# ws2812-cube-v1_3.net
KiCad netlist of a schematic drawn in EasyEDA
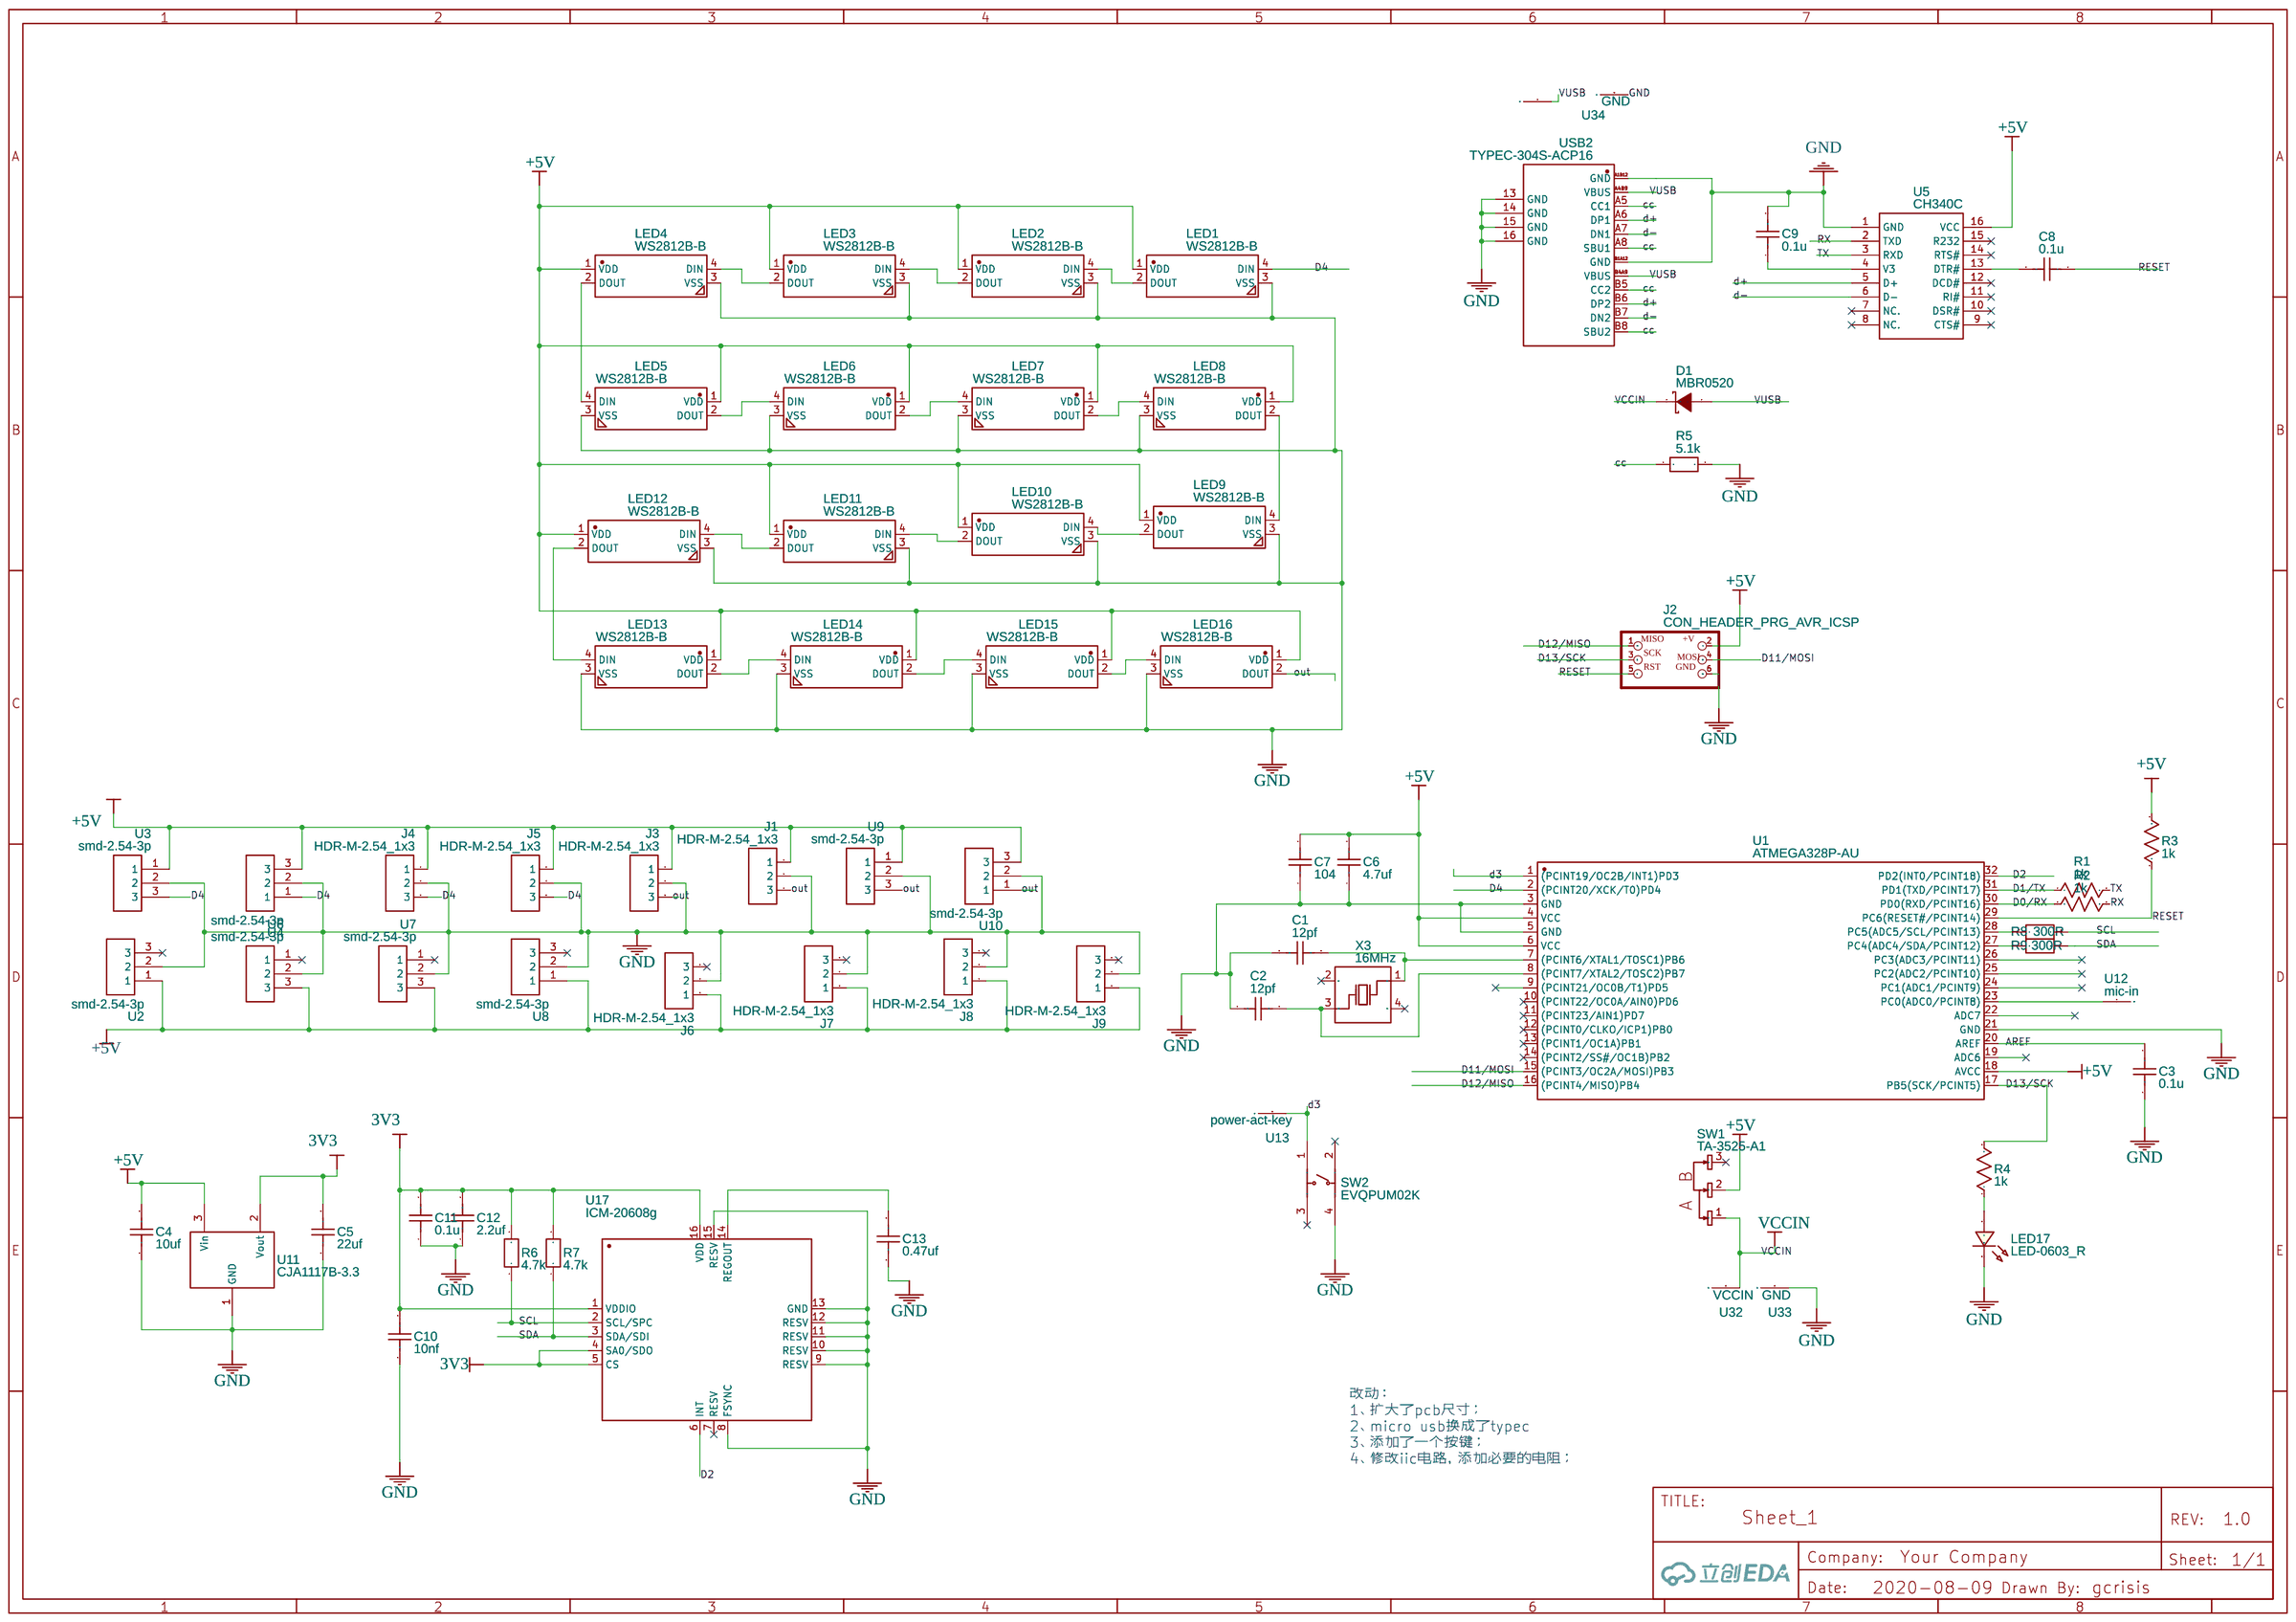
[diagram p0: schematic sheet]

(export (version "E")
  (design (tool "Eeschema 10.0.6"))
  (components
    (comp (ref "C1") (value "12pf") (libsource (lib "") (part "C_0603_US")))
    (comp (ref "C2") (value "12pf") (libsource (lib "") (part "C_0603_US")))
    (comp (ref "C3") (value "0.1u") (libsource (lib "") (part "C_0603_US_1")))
    (comp (ref "C4") (value "10uf") (libsource (lib "") (part "C_0603_US_1")))
    (comp (ref "C5") (value "22uf") (libsource (lib "") (part "C_0603_US_1")))
    (comp (ref "C6") (value "4.7uf") (libsource (lib "") (part "C_0603_US_1")))
    (comp (ref "C7") (value "104") (libsource (lib "") (part "C_0603_US_1")))
    (comp (ref "C8") (value "0.1u") (libsource (lib "") (part "C_0603_US")))
    (comp (ref "C9") (value "0.1u") (libsource (lib "") (part "C_0603_US_1")))
    (comp (ref "C10") (value "10nf") (libsource (lib "") (part "C_0603_US_1")))
    (comp (ref "C11") (value "0.1u") (libsource (lib "") (part "C_0603_US_1")))
    (comp (ref "C12") (value "2.2uf") (libsource (lib "") (part "C_0603_US_1")))
    (comp (ref "C13") (value "0.47uf") (libsource (lib "") (part "C_0603_US_1")))
    (comp (ref "D1")
      (value "MBR0520")
      (fields (field (name "BOM_Supplier Part") "C77335"))
      (libsource (lib "") (part "MBR0520"))
    )
    (comp (ref "J1")
      (value "HDR-M-2.54_1x3")
      (fields (field (name "BOM_Supplier Part") "C180248"))
      (libsource (lib "") (part "HDR-M-2.54_1x3_1"))
    )
    (comp (ref "J2") (value "CON_HEADER_PRG_AVR_ICSP") (libsource (lib "") (part "CON_HEADER_PRG_AVR_ICSP")))
    (comp (ref "J3")
      (value "HDR-M-2.54_1x3")
      (fields (field (name "BOM_Supplier Part") "C180248"))
      (libsource (lib "") (part "HDR-M-2.54_1x3_1"))
    )
    (comp (ref "J4")
      (value "HDR-M-2.54_1x3")
      (fields (field (name "BOM_Supplier Part") "C180248"))
      (libsource (lib "") (part "HDR-M-2.54_1x3_1"))
    )
    (comp (ref "J5")
      (value "HDR-M-2.54_1x3")
      (fields (field (name "BOM_Supplier Part") "C180248"))
      (libsource (lib "") (part "HDR-M-2.54_1x3_1"))
    )
    (comp (ref "J6")
      (value "HDR-M-2.54_1x3")
      (fields (field (name "BOM_Supplier Part") "C180248"))
      (libsource (lib "") (part "HDR-M-2.54_1x3"))
    )
    (comp (ref "J7")
      (value "HDR-M-2.54_1x3")
      (fields (field (name "BOM_Supplier Part") "C180248"))
      (libsource (lib "") (part "HDR-M-2.54_1x3"))
    )
    (comp (ref "J8")
      (value "HDR-M-2.54_1x3")
      (fields (field (name "BOM_Supplier Part") "C180248"))
      (libsource (lib "") (part "HDR-M-2.54_1x3"))
    )
    (comp (ref "J9")
      (value "HDR-M-2.54_1x3")
      (fields (field (name "BOM_Supplier Part") "C180248"))
      (libsource (lib "") (part "HDR-M-2.54_1x3"))
    )
    (comp (ref "LED1")
      (value "WS2812B-B")
      (fields (field (name "BOM_Supplier Part") "C114586"))
      (libsource (lib "") (part "WS2812B-B_1"))
    )
    (comp (ref "LED2")
      (value "WS2812B-B")
      (fields (field (name "BOM_Supplier Part") "C114586"))
      (libsource (lib "") (part "WS2812B-B_1"))
    )
    (comp (ref "LED3")
      (value "WS2812B-B")
      (fields (field (name "BOM_Supplier Part") "C114586"))
      (libsource (lib "") (part "WS2812B-B_1"))
    )
    (comp (ref "LED4")
      (value "WS2812B-B")
      (fields (field (name "BOM_Supplier Part") "C114586"))
      (libsource (lib "") (part "WS2812B-B_1"))
    )
    (comp (ref "LED5")
      (value "WS2812B-B")
      (fields (field (name "BOM_Supplier Part") "C114586"))
      (libsource (lib "") (part "WS2812B-B"))
    )
    (comp (ref "LED6")
      (value "WS2812B-B")
      (fields (field (name "BOM_Supplier Part") "C114586"))
      (libsource (lib "") (part "WS2812B-B"))
    )
    (comp (ref "LED7")
      (value "WS2812B-B")
      (fields (field (name "BOM_Supplier Part") "C114586"))
      (libsource (lib "") (part "WS2812B-B"))
    )
    (comp (ref "LED8")
      (value "WS2812B-B")
      (fields (field (name "BOM_Supplier Part") "C114586"))
      (libsource (lib "") (part "WS2812B-B"))
    )
    (comp (ref "LED9")
      (value "WS2812B-B")
      (fields (field (name "BOM_Supplier Part") "C114586"))
      (libsource (lib "") (part "WS2812B-B_1"))
    )
    (comp (ref "LED10")
      (value "WS2812B-B")
      (fields (field (name "BOM_Supplier Part") "C114586"))
      (libsource (lib "") (part "WS2812B-B_1"))
    )
    (comp (ref "LED11")
      (value "WS2812B-B")
      (fields (field (name "BOM_Supplier Part") "C114586"))
      (libsource (lib "") (part "WS2812B-B_1"))
    )
    (comp (ref "LED12")
      (value "WS2812B-B")
      (fields (field (name "BOM_Supplier Part") "C114586"))
      (libsource (lib "") (part "WS2812B-B_1"))
    )
    (comp (ref "LED13")
      (value "WS2812B-B")
      (fields (field (name "BOM_Supplier Part") "C114586"))
      (libsource (lib "") (part "WS2812B-B"))
    )
    (comp (ref "LED14")
      (value "WS2812B-B")
      (fields (field (name "BOM_Supplier Part") "C114586"))
      (libsource (lib "") (part "WS2812B-B"))
    )
    (comp (ref "LED15")
      (value "WS2812B-B")
      (fields (field (name "BOM_Supplier Part") "C114586"))
      (libsource (lib "") (part "WS2812B-B"))
    )
    (comp (ref "LED16")
      (value "WS2812B-B")
      (fields (field (name "BOM_Supplier Part") "C114586"))
      (libsource (lib "") (part "WS2812B-B"))
    )
    (comp (ref "LED17")
      (value "LED-0603_R")
      (fields
        (field (name "BOM_Manufacturer Part") "19-217/R6C-AL1M2VY/3T")
        (field (name "BOM_Supplier Part") "C72044")
      )
      (libsource (lib "") (part "LED-0603_R"))
    )
    (comp (ref "R1") (value "1k") (libsource (lib "") (part "R_0603_US")))
    (comp (ref "R2") (value "1k") (libsource (lib "") (part "R_0603_US")))
    (comp (ref "R3") (value "1k") (libsource (lib "") (part "R_0603_US_1")))
    (comp (ref "R4") (value "1k") (libsource (lib "") (part "R_0603_US_1")))
    (comp (ref "R5") (value "5.1k") (libsource (lib "") (part "R_0603_EU")))
    (comp (ref "R6") (value "4.7k") (libsource (lib "") (part "R_0603_EU_1")))
    (comp (ref "R7") (value "4.7k") (libsource (lib "") (part "R_0603_EU_1")))
    (comp (ref "R8") (value "300R") (libsource (lib "") (part "R_0603_EU")))
    (comp (ref "R9") (value "300R") (libsource (lib "") (part "R_0603_EU")))
    (comp (ref "SW1")
      (value "TA-3525-A1")
      (fields (field (name "BOM_Supplier Part") "C514018"))
      (libsource (lib "") (part "TA-3525-A1"))
    )
    (comp (ref "SW2")
      (value "EVQPUM02K")
      (fields (field (name "BOM_Supplier Part") "C388886"))
      (libsource (lib "") (part "EVQPUM02K"))
    )
    (comp (ref "U1")
      (value "ATMEGA328P-AU")
      (fields (field (name "BOM_Supplier Part") "C14877"))
      (libsource (lib "") (part "ATMEGA328P-AU"))
    )
    (comp (ref "U2") (value "smd-2.54-3p") (libsource (lib "") (part "smd-2.54-3p")))
    (comp (ref "U3") (value "smd-2.54-3p") (libsource (lib "") (part "smd-2.54-3p_1")))
    (comp (ref "U4") (value "smd-2.54-3p") (libsource (lib "") (part "smd-2.54-3p")))
    (comp (ref "U5")
      (value "CH340C")
      (fields (field (name "BOM_Supplier Part") "C84681"))
      (libsource (lib "") (part "CH340C"))
    )
    (comp (ref "U6") (value "smd-2.54-3p") (libsource (lib "") (part "smd-2.54-3p_1")))
    (comp (ref "U7") (value "smd-2.54-3p") (libsource (lib "") (part "smd-2.54-3p_1")))
    (comp (ref "U8") (value "smd-2.54-3p") (libsource (lib "") (part "smd-2.54-3p")))
    (comp (ref "U9") (value "smd-2.54-3p") (libsource (lib "") (part "smd-2.54-3p_1")))
    (comp (ref "U10") (value "smd-2.54-3p") (libsource (lib "") (part "smd-2.54-3p")))
    (comp (ref "U11")
      (value "CJA1117B-3.3")
      (fields (field (name "BOM_Supplier Part") "C24253"))
      (libsource (lib "") (part "CJA1117B-3.3"))
    )
    (comp (ref "U12") (value "mic-in") (libsource (lib "") (part "PAD_1")))
    (comp (ref "U13") (value "power-act-key") (libsource (lib "") (part "PAD")))
    (comp (ref "U17")
      (value "ICM-20608g")
      (fields (field (name "BOM_Manufacturer Part") "ICM-20602") (field (name "BOM_Supplier Part") "C97633"))
      (libsource (lib "") (part "ICM-20602"))
    )
    (comp (ref "U32") (value "VCCIN") (libsource (lib "") (part "PAD")))
    (comp (ref "U33") (value "GND") (libsource (lib "") (part "PAD")))
    (comp (ref "U34") (value "GND") (libsource (lib "") (part "PAD")))
    (comp (ref "U35") (value "VUSB") (libsource (lib "") (part "PAD")))
    (comp (ref "USB2")
      (value "TYPEC-304S-ACP16")
      (fields (field (name "BOM_Supplier Part") "C720630"))
      (libsource (lib "") (part "TYPEC-304S-ACP16"))
    )
    (comp (ref "X3")
      (value "16MHz")
      (fields
        (field (name "BOM_Manufacturer Part") "X1E0000210375000G")
        (field (name "BOM_Supplier Part") "C89379")
      )
      (libsource (lib "") (part "X1E0000210375000G"))
    )
  )
  (nets
    (net (code "1") (name "+5V") (class "Default")
      (node (ref "C4") (pin "2") (pinfunction "2_2") (pintype "unspecified"))
      (node (ref "C6") (pin "2") (pinfunction "2_2") (pintype "unspecified"))
      (node (ref "C7") (pin "2") (pinfunction "2_2") (pintype "unspecified"))
      (node (ref "J1") (pin "1") (pinfunction "1_1") (pintype "input"))
      (node (ref "J2") (pin "2") (pinfunction "+V_2") (pintype "unspecified"))
      (node (ref "J3") (pin "1") (pinfunction "1_1") (pintype "input"))
      (node (ref "J4") (pin "1") (pinfunction "1_1") (pintype "input"))
      (node (ref "J5") (pin "1") (pinfunction "1_1") (pintype "input"))
      (node (ref "J6") (pin "1") (pinfunction "1_1") (pintype "input"))
      (node (ref "J7") (pin "1") (pinfunction "1_1") (pintype "input"))
      (node (ref "J8") (pin "1") (pinfunction "1_1") (pintype "input"))
      (node (ref "J9") (pin "1") (pinfunction "1_1") (pintype "input"))
      (node (ref "LED1") (pin "1") (pinfunction "VDD_1") (pintype "unspecified"))
      (node (ref "LED10") (pin "1") (pinfunction "VDD_1") (pintype "unspecified"))
      (node (ref "LED11") (pin "1") (pinfunction "VDD_1") (pintype "unspecified"))
      (node (ref "LED12") (pin "1") (pinfunction "VDD_1") (pintype "unspecified"))
      (node (ref "LED13") (pin "1") (pinfunction "VDD_1") (pintype "unspecified"))
      (node (ref "LED14") (pin "1") (pinfunction "VDD_1") (pintype "unspecified"))
      (node (ref "LED15") (pin "1") (pinfunction "VDD_1") (pintype "unspecified"))
      (node (ref "LED16") (pin "1") (pinfunction "VDD_1") (pintype "unspecified"))
      (node (ref "LED2") (pin "1") (pinfunction "VDD_1") (pintype "unspecified"))
      (node (ref "LED3") (pin "1") (pinfunction "VDD_1") (pintype "unspecified"))
      (node (ref "LED4") (pin "1") (pinfunction "VDD_1") (pintype "unspecified"))
      (node (ref "LED5") (pin "1") (pinfunction "VDD_1") (pintype "unspecified"))
      (node (ref "LED6") (pin "1") (pinfunction "VDD_1") (pintype "unspecified"))
      (node (ref "LED7") (pin "1") (pinfunction "VDD_1") (pintype "unspecified"))
      (node (ref "LED8") (pin "1") (pinfunction "VDD_1") (pintype "unspecified"))
      (node (ref "LED9") (pin "1") (pinfunction "VDD_1") (pintype "unspecified"))
      (node (ref "R3") (pin "2") (pinfunction "2_2") (pintype "unspecified"))
      (node (ref "SW1") (pin "2") (pinfunction "2_2") (pintype "unspecified"))
      (node (ref "U1") (pin "18") (pinfunction "AVCC_18") (pintype "unspecified"))
      (node (ref "U1") (pin "4") (pinfunction "VCC_4") (pintype "unspecified"))
      (node (ref "U1") (pin "6") (pinfunction "VCC_6") (pintype "unspecified"))
      (node (ref "U10") (pin "3") (pinfunction "3_3") (pintype "unspecified"))
      (node (ref "U11") (pin "3") (pinfunction "Vin_3") (pintype "unspecified"))
      (node (ref "U2") (pin "1") (pinfunction "1_1") (pintype "unspecified"))
      (node (ref "U3") (pin "1") (pinfunction "1_1") (pintype "unspecified"))
      (node (ref "U4") (pin "3") (pinfunction "3_3") (pintype "unspecified"))
      (node (ref "U5") (pin "16") (pinfunction "VCC_16") (pintype "unspecified"))
      (node (ref "U6") (pin "3") (pinfunction "3_3") (pintype "unspecified"))
      (node (ref "U7") (pin "3") (pinfunction "3_3") (pintype "unspecified"))
      (node (ref "U8") (pin "1") (pinfunction "1_1") (pintype "unspecified"))
      (node (ref "U9") (pin "1") (pinfunction "1_1") (pintype "unspecified"))
    )
    (net (code "2") (name "/AREF") (class "Default")
      (node (ref "C3") (pin "2") (pinfunction "2_2") (pintype "unspecified"))
      (node (ref "U1") (pin "20") (pinfunction "AREF_20") (pintype "unspecified"))
    )
    (net (code "3") (name "/D0{slash}RX") (class "Default")
      (node (ref "R2") (pin "1") (pinfunction "1_1") (pintype "unspecified"))
      (node (ref "U1") (pin "30") (pinfunction "PD0(RXD/PCINT16)_30") (pintype "unspecified"))
    )
    (net (code "4") (name "/D1{slash}TX") (class "Default")
      (node (ref "R1") (pin "1") (pinfunction "1_1") (pintype "unspecified"))
      (node (ref "U1") (pin "31") (pinfunction "PD1(TXD/PCINT17)_31") (pintype "unspecified"))
    )
    (net (code "5") (name "/D2") (class "Default")
      (node (ref "U1") (pin "32") (pinfunction "PD2(INT0/PCINT18)_32") (pintype "unspecified"))
      (node (ref "U17") (pin "6") (pinfunction "INT_6") (pintype "unspecified"))
    )
    (net (code "6") (name "/D4") (class "Default")
      (node (ref "J4") (pin "3") (pinfunction "3_3") (pintype "input"))
      (node (ref "J5") (pin "3") (pinfunction "3_3") (pintype "input"))
      (node (ref "LED1") (pin "4") (pinfunction "DIN_4") (pintype "unspecified"))
      (node (ref "U1") (pin "2") (pinfunction "(PCINT20/XCK/T0)PD4_2") (pintype "unspecified"))
      (node (ref "U3") (pin "3") (pinfunction "3_3") (pintype "unspecified"))
      (node (ref "U4") (pin "1") (pinfunction "1_1") (pintype "unspecified"))
    )
    (net (code "7") (name "/D11{slash}MOSI") (class "Default")
      (node (ref "J2") (pin "4") (pinfunction "MOSI_4") (pintype "unspecified"))
      (node (ref "U1") (pin "15") (pinfunction "(PCINT3/OC2A/MOSI)PB3_15") (pintype "unspecified"))
    )
    (net (code "8") (name "/D12{slash}MISO") (class "Default")
      (node (ref "J2") (pin "1") (pinfunction "MISO_1") (pintype "unspecified"))
      (node (ref "U1") (pin "16") (pinfunction "(PCINT4/MISO)PB4_16") (pintype "unspecified"))
    )
    (net (code "9") (name "/D13{slash}SCK") (class "Default")
      (node (ref "J2") (pin "3") (pinfunction "SCK_3") (pintype "unspecified"))
      (node (ref "R4") (pin "2") (pinfunction "2_2") (pintype "unspecified"))
      (node (ref "U1") (pin "17") (pinfunction "PB5(SCK/PCINT5)_17") (pintype "unspecified"))
    )
    (net (code "10") (name "/RESET") (class "Default")
      (node (ref "C8") (pin "2") (pinfunction "2_2") (pintype "unspecified"))
      (node (ref "J2") (pin "5") (pinfunction "RST_5") (pintype "unspecified"))
      (node (ref "R3") (pin "1") (pinfunction "1_1") (pintype "unspecified"))
      (node (ref "U1") (pin "29") (pinfunction "PC6(RESET#/PCINT14)_29") (pintype "unspecified"))
    )
    (net (code "11") (name "/RX") (class "Default")
      (node (ref "R2") (pin "2") (pinfunction "2_2") (pintype "unspecified"))
      (node (ref "U5") (pin "2") (pinfunction "TXD_2") (pintype "unspecified"))
    )
    (net (code "12") (name "/SCL") (class "Default")
      (node (ref "R6") (pin "1") (pinfunction "1_1") (pintype "unspecified"))
      (node (ref "R8") (pin "2") (pinfunction "2_2") (pintype "unspecified"))
      (node (ref "U17") (pin "2") (pinfunction "SCL/SPC_2") (pintype "unspecified"))
    )
    (net (code "13") (name "/SDA") (class "Default")
      (node (ref "R7") (pin "1") (pinfunction "1_1") (pintype "unspecified"))
      (node (ref "R9") (pin "2") (pinfunction "2_2") (pintype "unspecified"))
      (node (ref "U17") (pin "3") (pinfunction "SDA/SDI_3") (pintype "unspecified"))
    )
    (net (code "14") (name "/TX") (class "Default")
      (node (ref "R1") (pin "2") (pinfunction "2_2") (pintype "unspecified"))
      (node (ref "U5") (pin "3") (pinfunction "RXD_3") (pintype "unspecified"))
    )
    (net (code "15") (name "/VUSB") (class "Default")
      (node (ref "D1") (pin "2") (pinfunction "A_2") (pintype "unspecified"))
      (node (ref "U35") (pin "P$1") (pinfunction "P$1_P$1") (pintype "unspecified"))
      (node (ref "USB2") (pin "A4B9") (pinfunction "VBUS_A4B9") (pintype "unspecified"))
      (node (ref "USB2") (pin "B4A9") (pinfunction "VBUS_B4A9") (pintype "unspecified"))
    )
    (net (code "16") (name "/cc") (class "Default")
      (node (ref "R5") (pin "1") (pinfunction "1_1") (pintype "unspecified"))
      (node (ref "USB2") (pin "A5") (pinfunction "CC1_A5") (pintype "unspecified"))
      (node (ref "USB2") (pin "A8") (pinfunction "SBU1_A8") (pintype "unspecified"))
      (node (ref "USB2") (pin "B5") (pinfunction "CC2_B5") (pintype "unspecified"))
      (node (ref "USB2") (pin "B8") (pinfunction "SBU2_B8") (pintype "unspecified"))
    )
    (net (code "17") (name "/d+") (class "Default")
      (node (ref "U5") (pin "5") (pinfunction "D+_5") (pintype "unspecified"))
      (node (ref "USB2") (pin "A6") (pinfunction "DP1_A6") (pintype "unspecified"))
      (node (ref "USB2") (pin "B6") (pinfunction "DP2_B6") (pintype "unspecified"))
    )
    (net (code "18") (name "/d-") (class "Default")
      (node (ref "U5") (pin "6") (pinfunction "D-_6") (pintype "unspecified"))
      (node (ref "USB2") (pin "A7") (pinfunction "DN1_A7") (pintype "unspecified"))
      (node (ref "USB2") (pin "B7") (pinfunction "DN2_B7") (pintype "unspecified"))
    )
    (net (code "19") (name "/d3") (class "Default")
      (node (ref "SW2") (pin "1") (pinfunction "1_1") (pintype "unspecified"))
      (node (ref "U1") (pin "1") (pinfunction "(PCINT19/OC2B/INT1)PD3_1") (pintype "unspecified"))
      (node (ref "U13") (pin "P$1") (pinfunction "P$1_P$1") (pintype "unspecified"))
    )
    (net (code "20") (name "/out") (class "Default")
      (node (ref "J1") (pin "3") (pinfunction "3_3") (pintype "input"))
      (node (ref "J3") (pin "3") (pinfunction "3_3") (pintype "input"))
      (node (ref "LED16") (pin "2") (pinfunction "DOUT_2") (pintype "unspecified"))
      (node (ref "U10") (pin "1") (pinfunction "1_1") (pintype "unspecified"))
      (node (ref "U9") (pin "3") (pinfunction "3_3") (pintype "unspecified"))
    )
    (net (code "21") (name "3V3") (class "Default")
      (node (ref "C10") (pin "2") (pinfunction "2_2") (pintype "unspecified"))
      (node (ref "C11") (pin "2") (pinfunction "2_2") (pintype "unspecified"))
      (node (ref "C12") (pin "2") (pinfunction "2_2") (pintype "unspecified"))
      (node (ref "C5") (pin "2") (pinfunction "2_2") (pintype "unspecified"))
      (node (ref "R6") (pin "2") (pinfunction "2_2") (pintype "unspecified"))
      (node (ref "R7") (pin "2") (pinfunction "2_2") (pintype "unspecified"))
      (node (ref "U11") (pin "2") (pinfunction "Vout_2") (pintype "unspecified"))
      (node (ref "U17") (pin "1") (pinfunction "VDDIO_1") (pintype "unspecified"))
      (node (ref "U17") (pin "16") (pinfunction "VDD_16") (pintype "unspecified"))
      (node (ref "U17") (pin "4") (pinfunction "SA0/SDO_4") (pintype "unspecified"))
      (node (ref "U17") (pin "5") (pinfunction "CS_5") (pintype "unspecified"))
    )
    (net (code "22") (name "GND") (class "Default")
      (node (ref "C1") (pin "1") (pinfunction "1_1") (pintype "unspecified"))
      (node (ref "C10") (pin "1") (pinfunction "1_1") (pintype "unspecified"))
      (node (ref "C11") (pin "1") (pinfunction "1_1") (pintype "unspecified"))
      (node (ref "C12") (pin "1") (pinfunction "1_1") (pintype "unspecified"))
      (node (ref "C13") (pin "1") (pinfunction "1_1") (pintype "unspecified"))
      (node (ref "C2") (pin "1") (pinfunction "1_1") (pintype "unspecified"))
      (node (ref "C3") (pin "1") (pinfunction "1_1") (pintype "unspecified"))
      (node (ref "C4") (pin "1") (pinfunction "1_1") (pintype "unspecified"))
      (node (ref "C5") (pin "1") (pinfunction "1_1") (pintype "unspecified"))
      (node (ref "C6") (pin "1") (pinfunction "1_1") (pintype "unspecified"))
      (node (ref "C7") (pin "1") (pinfunction "1_1") (pintype "unspecified"))
      (node (ref "C9") (pin "2") (pinfunction "2_2") (pintype "unspecified"))
      (node (ref "J1") (pin "2") (pinfunction "2_2") (pintype "input"))
      (node (ref "J2") (pin "6") (pinfunction "GND_6") (pintype "unspecified"))
      (node (ref "J3") (pin "2") (pinfunction "2_2") (pintype "input"))
      (node (ref "J4") (pin "2") (pinfunction "2_2") (pintype "input"))
      (node (ref "J5") (pin "2") (pinfunction "2_2") (pintype "input"))
      (node (ref "J6") (pin "2") (pinfunction "2_2") (pintype "input"))
      (node (ref "J7") (pin "2") (pinfunction "2_2") (pintype "input"))
      (node (ref "J8") (pin "2") (pinfunction "2_2") (pintype "input"))
      (node (ref "J9") (pin "2") (pinfunction "2_2") (pintype "input"))
      (node (ref "LED1") (pin "3") (pinfunction "VSS_3") (pintype "unspecified"))
      (node (ref "LED10") (pin "3") (pinfunction "VSS_3") (pintype "unspecified"))
      (node (ref "LED11") (pin "3") (pinfunction "VSS_3") (pintype "unspecified"))
      (node (ref "LED12") (pin "3") (pinfunction "VSS_3") (pintype "unspecified"))
      (node (ref "LED13") (pin "3") (pinfunction "VSS_3") (pintype "unspecified"))
      (node (ref "LED14") (pin "3") (pinfunction "VSS_3") (pintype "unspecified"))
      (node (ref "LED15") (pin "3") (pinfunction "VSS_3") (pintype "unspecified"))
      (node (ref "LED16") (pin "3") (pinfunction "VSS_3") (pintype "unspecified"))
      (node (ref "LED17") (pin "2") (pinfunction "2_2") (pintype "unspecified"))
      (node (ref "LED2") (pin "3") (pinfunction "VSS_3") (pintype "unspecified"))
      (node (ref "LED3") (pin "3") (pinfunction "VSS_3") (pintype "unspecified"))
      (node (ref "LED4") (pin "3") (pinfunction "VSS_3") (pintype "unspecified"))
      (node (ref "LED5") (pin "3") (pinfunction "VSS_3") (pintype "unspecified"))
      (node (ref "LED6") (pin "3") (pinfunction "VSS_3") (pintype "unspecified"))
      (node (ref "LED7") (pin "3") (pinfunction "VSS_3") (pintype "unspecified"))
      (node (ref "LED8") (pin "3") (pinfunction "VSS_3") (pintype "unspecified"))
      (node (ref "LED9") (pin "3") (pinfunction "VSS_3") (pintype "unspecified"))
      (node (ref "R5") (pin "2") (pinfunction "2_2") (pintype "unspecified"))
      (node (ref "SW2") (pin "4") (pinfunction "4_4") (pintype "unspecified"))
      (node (ref "U1") (pin "21") (pinfunction "GND_21") (pintype "unspecified"))
      (node (ref "U1") (pin "3") (pinfunction "GND_3") (pintype "unspecified"))
      (node (ref "U1") (pin "5") (pinfunction "GND_5") (pintype "unspecified"))
      (node (ref "U10") (pin "2") (pinfunction "2_2") (pintype "unspecified"))
      (node (ref "U11") (pin "1") (pinfunction "GND_1") (pintype "unspecified"))
      (node (ref "U17") (pin "10") (pinfunction "RESV_10") (pintype "unspecified"))
      (node (ref "U17") (pin "11") (pinfunction "RESV_11") (pintype "unspecified"))
      (node (ref "U17") (pin "12") (pinfunction "RESV_12") (pintype "unspecified"))
      (node (ref "U17") (pin "13") (pinfunction "GND_13") (pintype "unspecified"))
      (node (ref "U17") (pin "15") (pinfunction "RESV_15") (pintype "unspecified"))
      (node (ref "U17") (pin "8") (pinfunction "FSYNC_8") (pintype "unspecified"))
      (node (ref "U17") (pin "9") (pinfunction "RESV_9") (pintype "unspecified"))
      (node (ref "U2") (pin "2") (pinfunction "2_2") (pintype "unspecified"))
      (node (ref "U3") (pin "2") (pinfunction "2_2") (pintype "unspecified"))
      (node (ref "U33") (pin "P$1") (pinfunction "P$1_P$1") (pintype "unspecified"))
      (node (ref "U34") (pin "P$1") (pinfunction "P$1_P$1") (pintype "unspecified"))
      (node (ref "U4") (pin "2") (pinfunction "2_2") (pintype "unspecified"))
      (node (ref "U5") (pin "1") (pinfunction "GND_1") (pintype "unspecified"))
      (node (ref "U6") (pin "2") (pinfunction "2_2") (pintype "unspecified"))
      (node (ref "U7") (pin "2") (pinfunction "2_2") (pintype "unspecified"))
      (node (ref "U8") (pin "2") (pinfunction "2_2") (pintype "unspecified"))
      (node (ref "U9") (pin "2") (pinfunction "2_2") (pintype "unspecified"))
      (node (ref "USB2") (pin "13") (pinfunction "GND_13") (pintype "unspecified"))
      (node (ref "USB2") (pin "14") (pinfunction "GND_14") (pintype "unspecified"))
      (node (ref "USB2") (pin "15") (pinfunction "GND_15") (pintype "unspecified"))
      (node (ref "USB2") (pin "16") (pinfunction "GND_16") (pintype "unspecified"))
      (node (ref "USB2") (pin "A1B12") (pinfunction "GND_A1B12") (pintype "unspecified"))
      (node (ref "USB2") (pin "B1A12") (pinfunction "GND_B1A12") (pintype "unspecified"))
    )
    (net (code "23") (name "Net-(LED1-DOUT)") (class "Default")
      (node (ref "LED1") (pin "2") (pinfunction "DOUT_2") (pintype "unspecified"))
      (node (ref "LED2") (pin "4") (pinfunction "DIN_4") (pintype "unspecified"))
    )
    (net (code "24") (name "Net-(LED2-DOUT)") (class "Default")
      (node (ref "LED2") (pin "2") (pinfunction "DOUT_2") (pintype "unspecified"))
      (node (ref "LED3") (pin "4") (pinfunction "DIN_4") (pintype "unspecified"))
    )
    (net (code "25") (name "Net-(LED3-DOUT)") (class "Default")
      (node (ref "LED3") (pin "2") (pinfunction "DOUT_2") (pintype "unspecified"))
      (node (ref "LED4") (pin "4") (pinfunction "DIN_4") (pintype "unspecified"))
    )
    (net (code "26") (name "Net-(LED4-DOUT)") (class "Default")
      (node (ref "LED4") (pin "2") (pinfunction "DOUT_2") (pintype "unspecified"))
      (node (ref "LED5") (pin "4") (pinfunction "DIN_4") (pintype "unspecified"))
    )
    (net (code "27") (name "Net-(LED5-DOUT)") (class "Default")
      (node (ref "LED5") (pin "2") (pinfunction "DOUT_2") (pintype "unspecified"))
      (node (ref "LED6") (pin "4") (pinfunction "DIN_4") (pintype "unspecified"))
    )
    (net (code "28") (name "Net-(LED6-DOUT)") (class "Default")
      (node (ref "LED6") (pin "2") (pinfunction "DOUT_2") (pintype "unspecified"))
      (node (ref "LED7") (pin "4") (pinfunction "DIN_4") (pintype "unspecified"))
    )
    (net (code "29") (name "Net-(LED7-DOUT)") (class "Default")
      (node (ref "LED7") (pin "2") (pinfunction "DOUT_2") (pintype "unspecified"))
      (node (ref "LED8") (pin "4") (pinfunction "DIN_4") (pintype "unspecified"))
    )
    (net (code "30") (name "Net-(LED8-DOUT)") (class "Default")
      (node (ref "LED8") (pin "2") (pinfunction "DOUT_2") (pintype "unspecified"))
      (node (ref "LED9") (pin "4") (pinfunction "DIN_4") (pintype "unspecified"))
    )
    (net (code "31") (name "Net-(LED10-DIN)") (class "Default")
      (node (ref "LED10") (pin "4") (pinfunction "DIN_4") (pintype "unspecified"))
      (node (ref "LED9") (pin "2") (pinfunction "DOUT_2") (pintype "unspecified"))
    )
    (net (code "32") (name "Net-(LED10-DOUT)") (class "Default")
      (node (ref "LED10") (pin "2") (pinfunction "DOUT_2") (pintype "unspecified"))
      (node (ref "LED11") (pin "4") (pinfunction "DIN_4") (pintype "unspecified"))
    )
    (net (code "33") (name "Net-(LED11-DOUT)") (class "Default")
      (node (ref "LED11") (pin "2") (pinfunction "DOUT_2") (pintype "unspecified"))
      (node (ref "LED12") (pin "4") (pinfunction "DIN_4") (pintype "unspecified"))
    )
    (net (code "34") (name "Net-(LED12-DOUT)") (class "Default")
      (node (ref "LED12") (pin "2") (pinfunction "DOUT_2") (pintype "unspecified"))
      (node (ref "LED13") (pin "4") (pinfunction "DIN_4") (pintype "unspecified"))
    )
    (net (code "35") (name "Net-(LED13-DOUT)") (class "Default")
      (node (ref "LED13") (pin "2") (pinfunction "DOUT_2") (pintype "unspecified"))
      (node (ref "LED14") (pin "4") (pinfunction "DIN_4") (pintype "unspecified"))
    )
    (net (code "36") (name "Net-(LED14-DOUT)") (class "Default")
      (node (ref "LED14") (pin "2") (pinfunction "DOUT_2") (pintype "unspecified"))
      (node (ref "LED15") (pin "4") (pinfunction "DIN_4") (pintype "unspecified"))
    )
    (net (code "37") (name "Net-(LED15-DOUT)") (class "Default")
      (node (ref "LED15") (pin "2") (pinfunction "DOUT_2") (pintype "unspecified"))
      (node (ref "LED16") (pin "4") (pinfunction "DIN_4") (pintype "unspecified"))
    )
    (net (code "38") (name "Net-(LED17-Pad1)") (class "Default")
      (node (ref "LED17") (pin "1") (pinfunction "1_1") (pintype "unspecified"))
      (node (ref "R4") (pin "1") (pinfunction "1_1") (pintype "unspecified"))
    )
    (net (code "39") (name "Net-(U1-(PCINT6{slash}XTAL1{slash}TOSC1)PB6)") (class "Default")
      (node (ref "C1") (pin "2") (pinfunction "2_2") (pintype "unspecified"))
      (node (ref "U1") (pin "7") (pinfunction "(PCINT6/XTAL1/TOSC1)PB6_7") (pintype "unspecified"))
      (node (ref "X3") (pin "1") (pinfunction "OSC1_1") (pintype "unspecified"))
    )
    (net (code "40") (name "Net-(U1-(PCINT7{slash}XTAL2{slash}TOSC2)PB7)") (class "Default")
      (node (ref "C2") (pin "2") (pinfunction "2_2") (pintype "unspecified"))
      (node (ref "U1") (pin "8") (pinfunction "(PCINT7/XTAL2/TOSC2)PB7_8") (pintype "unspecified"))
      (node (ref "X3") (pin "3") (pinfunction "OSC2_3") (pintype "unspecified"))
    )
    (net (code "41") (name "Net-(U1-PC0(ADC0{slash}PCINT8))") (class "Default")
      (node (ref "U1") (pin "23") (pinfunction "PC0(ADC0/PCINT8)_23") (pintype "unspecified"))
      (node (ref "U12") (pin "P$1") (pinfunction "P$1_P$1") (pintype "unspecified"))
    )
    (net (code "42") (name "Net-(U1-PC4(ADC4{slash}SDA{slash}PCINT12))") (class "Default")
      (node (ref "R9") (pin "1") (pinfunction "1_1") (pintype "unspecified"))
      (node (ref "U1") (pin "27") (pinfunction "PC4(ADC4/SDA/PCINT12)_27") (pintype "unspecified"))
    )
    (net (code "43") (name "Net-(U1-PC5(ADC5{slash}SCL{slash}PCINT13))") (class "Default")
      (node (ref "R8") (pin "1") (pinfunction "1_1") (pintype "unspecified"))
      (node (ref "U1") (pin "28") (pinfunction "PC5(ADC5/SCL/PCINT13)_28") (pintype "unspecified"))
    )
    (net (code "44") (name "Net-(U5-DTR#)") (class "Default")
      (node (ref "C8") (pin "1") (pinfunction "1_1") (pintype "unspecified"))
      (node (ref "U5") (pin "13") (pinfunction "DTR#_13") (pintype "unspecified"))
    )
    (net (code "45") (name "Net-(U5-V3)") (class "Default")
      (node (ref "C9") (pin "1") (pinfunction "1_1") (pintype "unspecified"))
      (node (ref "U5") (pin "4") (pinfunction "V3_4") (pintype "unspecified"))
    )
    (net (code "46") (name "Net-(U17-REGOUT)") (class "Default")
      (node (ref "C13") (pin "2") (pinfunction "2_2") (pintype "unspecified"))
      (node (ref "U17") (pin "14") (pinfunction "REGOUT_14") (pintype "unspecified"))
    )
    (net (code "47") (name "VCCIN") (class "Default")
      (node (ref "D1") (pin "1") (pinfunction "K_1") (pintype "unspecified"))
      (node (ref "SW1") (pin "1") (pinfunction "1_1") (pintype "unspecified"))
      (node (ref "U32") (pin "P$1") (pinfunction "P$1_P$1") (pintype "unspecified"))
    )
    (net (code "48") (name "unconnected-(J6-Pad3)") (class "Default")
      (node (ref "J6") (pin "3") (pinfunction "3_3") (pintype "input+no_connect"))
    )
    (net (code "49") (name "unconnected-(J7-Pad3)") (class "Default")
      (node (ref "J7") (pin "3") (pinfunction "3_3") (pintype "input+no_connect"))
    )
    (net (code "50") (name "unconnected-(J8-Pad3)") (class "Default")
      (node (ref "J8") (pin "3") (pinfunction "3_3") (pintype "input+no_connect"))
    )
    (net (code "51") (name "unconnected-(J9-Pad3)") (class "Default")
      (node (ref "J9") (pin "3") (pinfunction "3_3") (pintype "input+no_connect"))
    )
    (net (code "52") (name "unconnected-(SW1-Pad3)") (class "Default")
      (node (ref "SW1") (pin "3") (pinfunction "3_3") (pintype "unspecified+no_connect"))
    )
    (net (code "53") (name "unconnected-(SW2-Pad2)") (class "Default")
      (node (ref "SW2") (pin "2") (pinfunction "2_2") (pintype "unspecified+no_connect"))
    )
    (net (code "54") (name "unconnected-(SW2-Pad3)") (class "Default")
      (node (ref "SW2") (pin "3") (pinfunction "3_3") (pintype "unspecified+no_connect"))
    )
    (net (code "55") (name "unconnected-(U1-(PCINT0{slash}CLKO{slash}ICP1)PB0-Pad12)") (class "Default")
      (node (ref "U1") (pin "12") (pinfunction "(PCINT0/CLKO/ICP1)PB0_12") (pintype "unspecified+no_connect"))
    )
    (net (code "56") (name "unconnected-(U1-(PCINT1{slash}OC1A)PB1-Pad13)") (class "Default")
      (node (ref "U1") (pin "13") (pinfunction "(PCINT1/OC1A)PB1_13") (pintype "unspecified+no_connect"))
    )
    (net (code "57") (name "unconnected-(U1-(PCINT2{slash}SS#{slash}OC1B)PB2-Pad14)") (class "Default")
      (node (ref "U1") (pin "14") (pinfunction "(PCINT2/SS#/OC1B)PB2_14") (pintype "unspecified+no_connect"))
    )
    (net (code "58") (name "unconnected-(U1-(PCINT21{slash}OC0B{slash}T1)PD5-Pad9)") (class "Default")
      (node (ref "U1") (pin "9") (pinfunction "(PCINT21/OC0B/T1)PD5_9") (pintype "unspecified+no_connect"))
    )
    (net (code "59") (name "unconnected-(U1-(PCINT22{slash}OC0A{slash}AIN0)PD6-Pad10)") (class "Default")
      (node (ref "U1") (pin "10") (pinfunction "(PCINT22/OC0A/AIN0)PD6_10") (pintype "unspecified+no_connect"))
    )
    (net (code "60") (name "unconnected-(U1-(PCINT23{slash}AIN1)PD7-Pad11)") (class "Default")
      (node (ref "U1") (pin "11") (pinfunction "(PCINT23/AIN1)PD7_11") (pintype "unspecified+no_connect"))
    )
    (net (code "61") (name "unconnected-(U1-ADC6-Pad19)") (class "Default")
      (node (ref "U1") (pin "19") (pinfunction "ADC6_19") (pintype "unspecified+no_connect"))
    )
    (net (code "62") (name "unconnected-(U1-ADC7-Pad22)") (class "Default")
      (node (ref "U1") (pin "22") (pinfunction "ADC7_22") (pintype "unspecified+no_connect"))
    )
    (net (code "63") (name "unconnected-(U1-PC1(ADC1{slash}PCINT9)-Pad24)") (class "Default")
      (node (ref "U1") (pin "24") (pinfunction "PC1(ADC1/PCINT9)_24") (pintype "unspecified+no_connect"))
    )
    (net (code "64") (name "unconnected-(U1-PC2(ADC2{slash}PCINT10)-Pad25)") (class "Default")
      (node (ref "U1") (pin "25") (pinfunction "PC2(ADC2/PCINT10)_25") (pintype "unspecified+no_connect"))
    )
    (net (code "65") (name "unconnected-(U1-PC3(ADC3{slash}PCINT11)-Pad26)") (class "Default")
      (node (ref "U1") (pin "26") (pinfunction "PC3(ADC3/PCINT11)_26") (pintype "unspecified+no_connect"))
    )
    (net (code "66") (name "unconnected-(U2-Pad3)") (class "Default")
      (node (ref "U2") (pin "3") (pinfunction "3_3") (pintype "unspecified+no_connect"))
    )
    (net (code "67") (name "unconnected-(U5-CTS#-Pad9)") (class "Default")
      (node (ref "U5") (pin "9") (pinfunction "CTS#_9") (pintype "unspecified+no_connect"))
    )
    (net (code "68") (name "unconnected-(U5-DCD#-Pad12)") (class "Default")
      (node (ref "U5") (pin "12") (pinfunction "DCD#_12") (pintype "unspecified+no_connect"))
    )
    (net (code "69") (name "unconnected-(U5-DSR#-Pad10)") (class "Default")
      (node (ref "U5") (pin "10") (pinfunction "DSR#_10") (pintype "unspecified+no_connect"))
    )
    (net (code "70") (name "unconnected-(U5-NC.-Pad7)") (class "Default")
      (node (ref "U5") (pin "7") (pinfunction "NC._7") (pintype "unspecified+no_connect"))
    )
    (net (code "71") (name "unconnected-(U5-NC.-Pad8)") (class "Default")
      (node (ref "U5") (pin "8") (pinfunction "NC._8") (pintype "unspecified+no_connect"))
    )
    (net (code "72") (name "unconnected-(U5-R232-Pad15)") (class "Default")
      (node (ref "U5") (pin "15") (pinfunction "R232_15") (pintype "unspecified+no_connect"))
    )
    (net (code "73") (name "unconnected-(U5-RI#-Pad11)") (class "Default")
      (node (ref "U5") (pin "11") (pinfunction "RI#_11") (pintype "unspecified+no_connect"))
    )
    (net (code "74") (name "unconnected-(U5-RTS#-Pad14)") (class "Default")
      (node (ref "U5") (pin "14") (pinfunction "RTS#_14") (pintype "unspecified+no_connect"))
    )
    (net (code "75") (name "unconnected-(U6-Pad1)") (class "Default")
      (node (ref "U6") (pin "1") (pinfunction "1_1") (pintype "unspecified+no_connect"))
    )
    (net (code "76") (name "unconnected-(U7-Pad1)") (class "Default")
      (node (ref "U7") (pin "1") (pinfunction "1_1") (pintype "unspecified+no_connect"))
    )
    (net (code "77") (name "unconnected-(U8-Pad3)") (class "Default")
      (node (ref "U8") (pin "3") (pinfunction "3_3") (pintype "unspecified+no_connect"))
    )
    (net (code "78") (name "unconnected-(U17-RESV-Pad7)") (class "Default")
      (node (ref "U17") (pin "7") (pinfunction "RESV_7") (pintype "unspecified+no_connect"))
    )
    (net (code "79") (name "unconnected-(X3-GND-Pad2)") (class "Default")
      (node (ref "X3") (pin "2") (pinfunction "GND_2") (pintype "unspecified+no_connect"))
    )
    (net (code "80") (name "unconnected-(X3-GND-Pad4)") (class "Default")
      (node (ref "X3") (pin "4") (pinfunction "GND_4") (pintype "unspecified+no_connect"))
    )
  )
)
